# Xibeca44.net
KiCad netlist of a schematic drawn in EAGLE
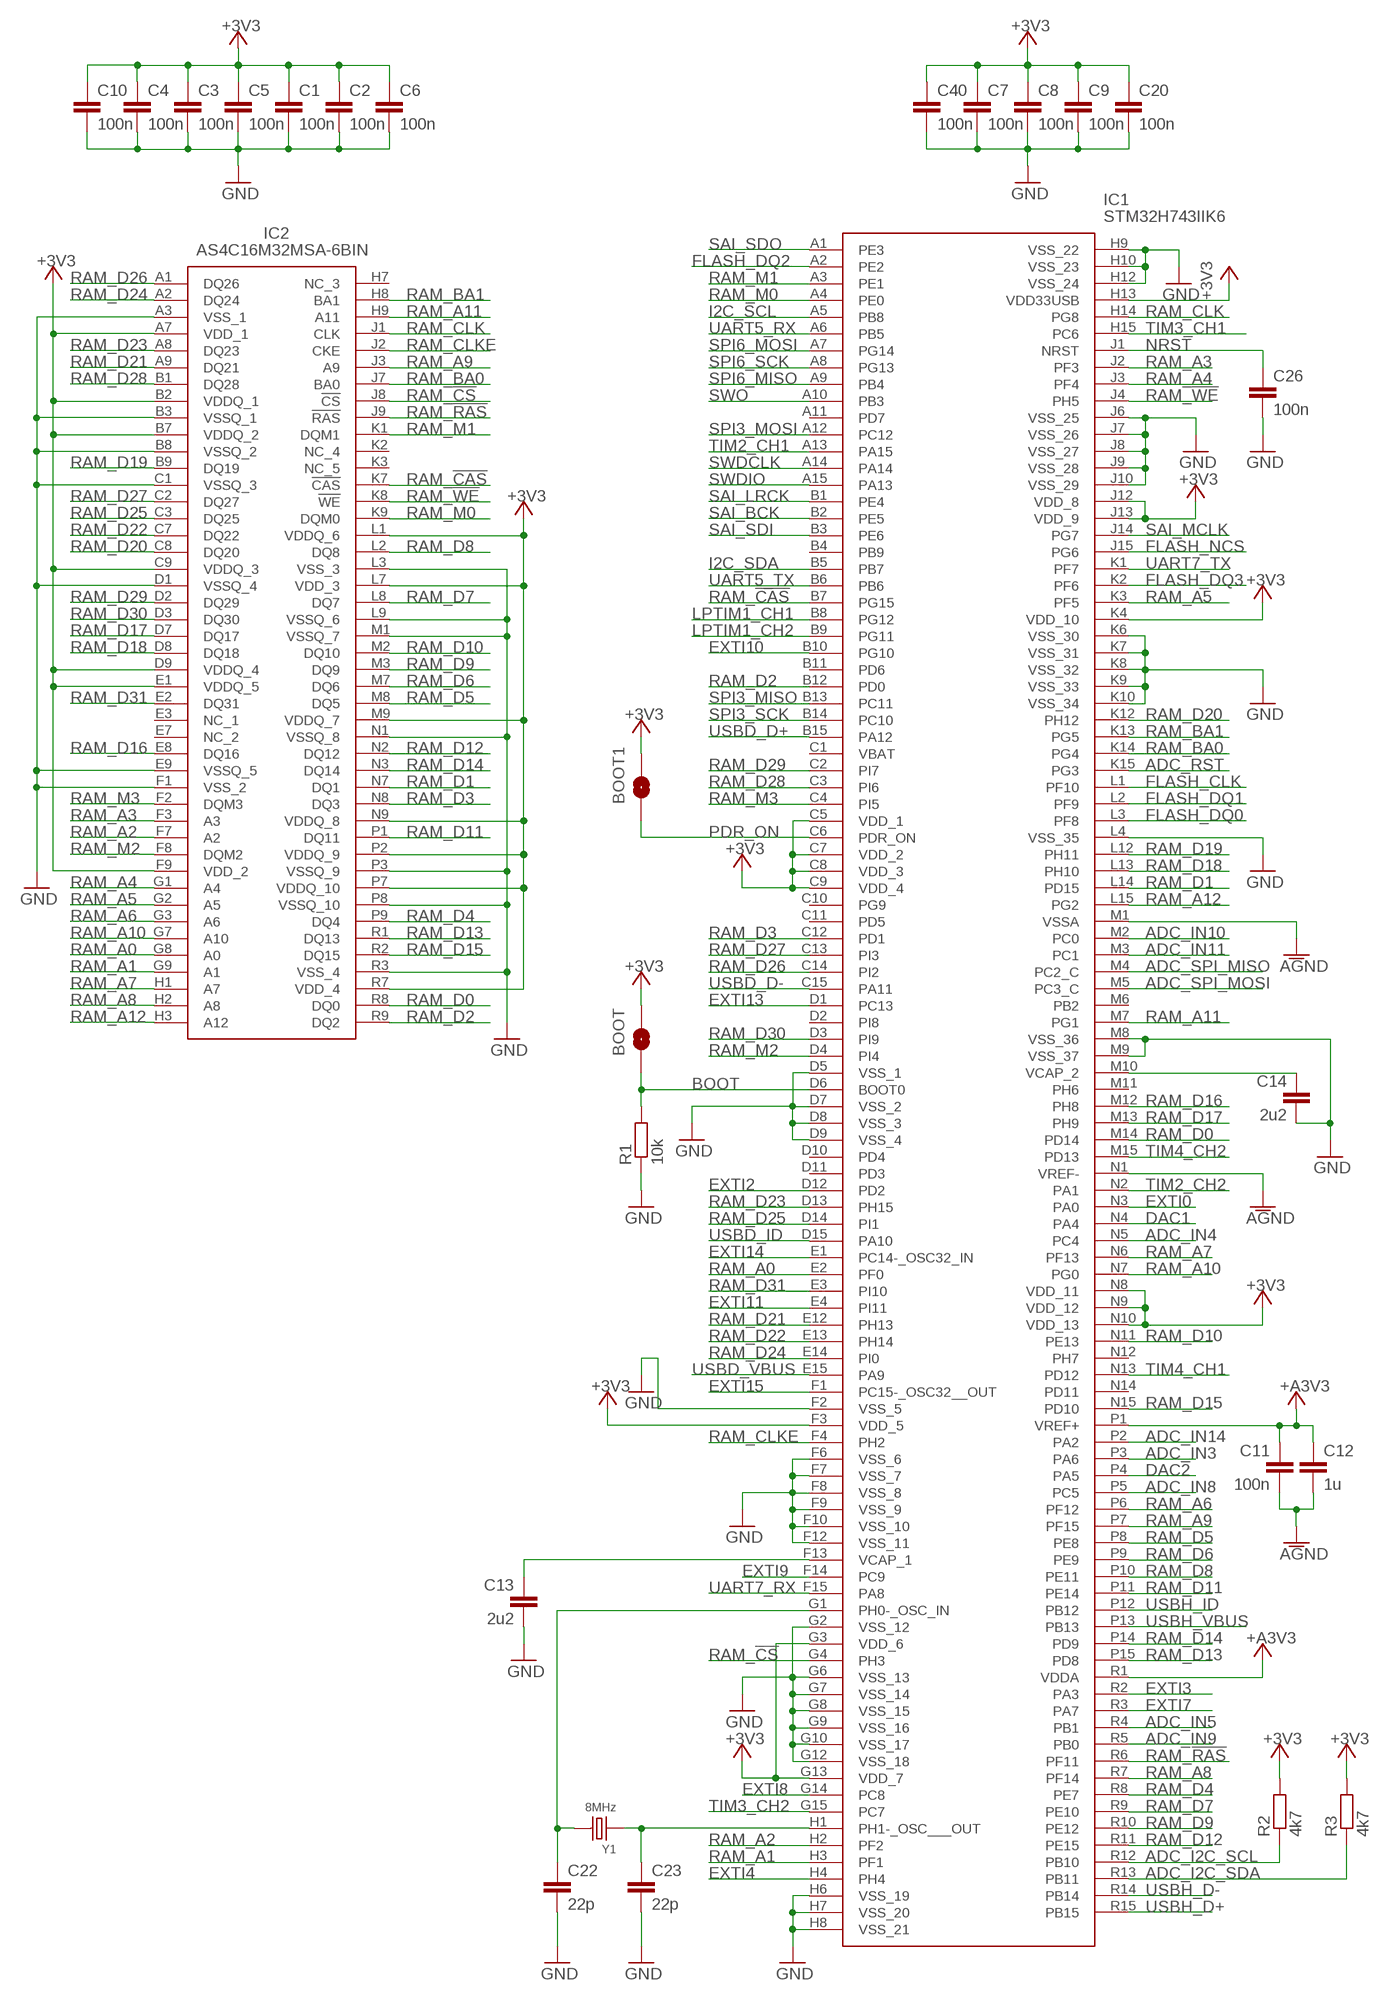
[diagram p0: schematic, sheet 1, part 1 of 2]
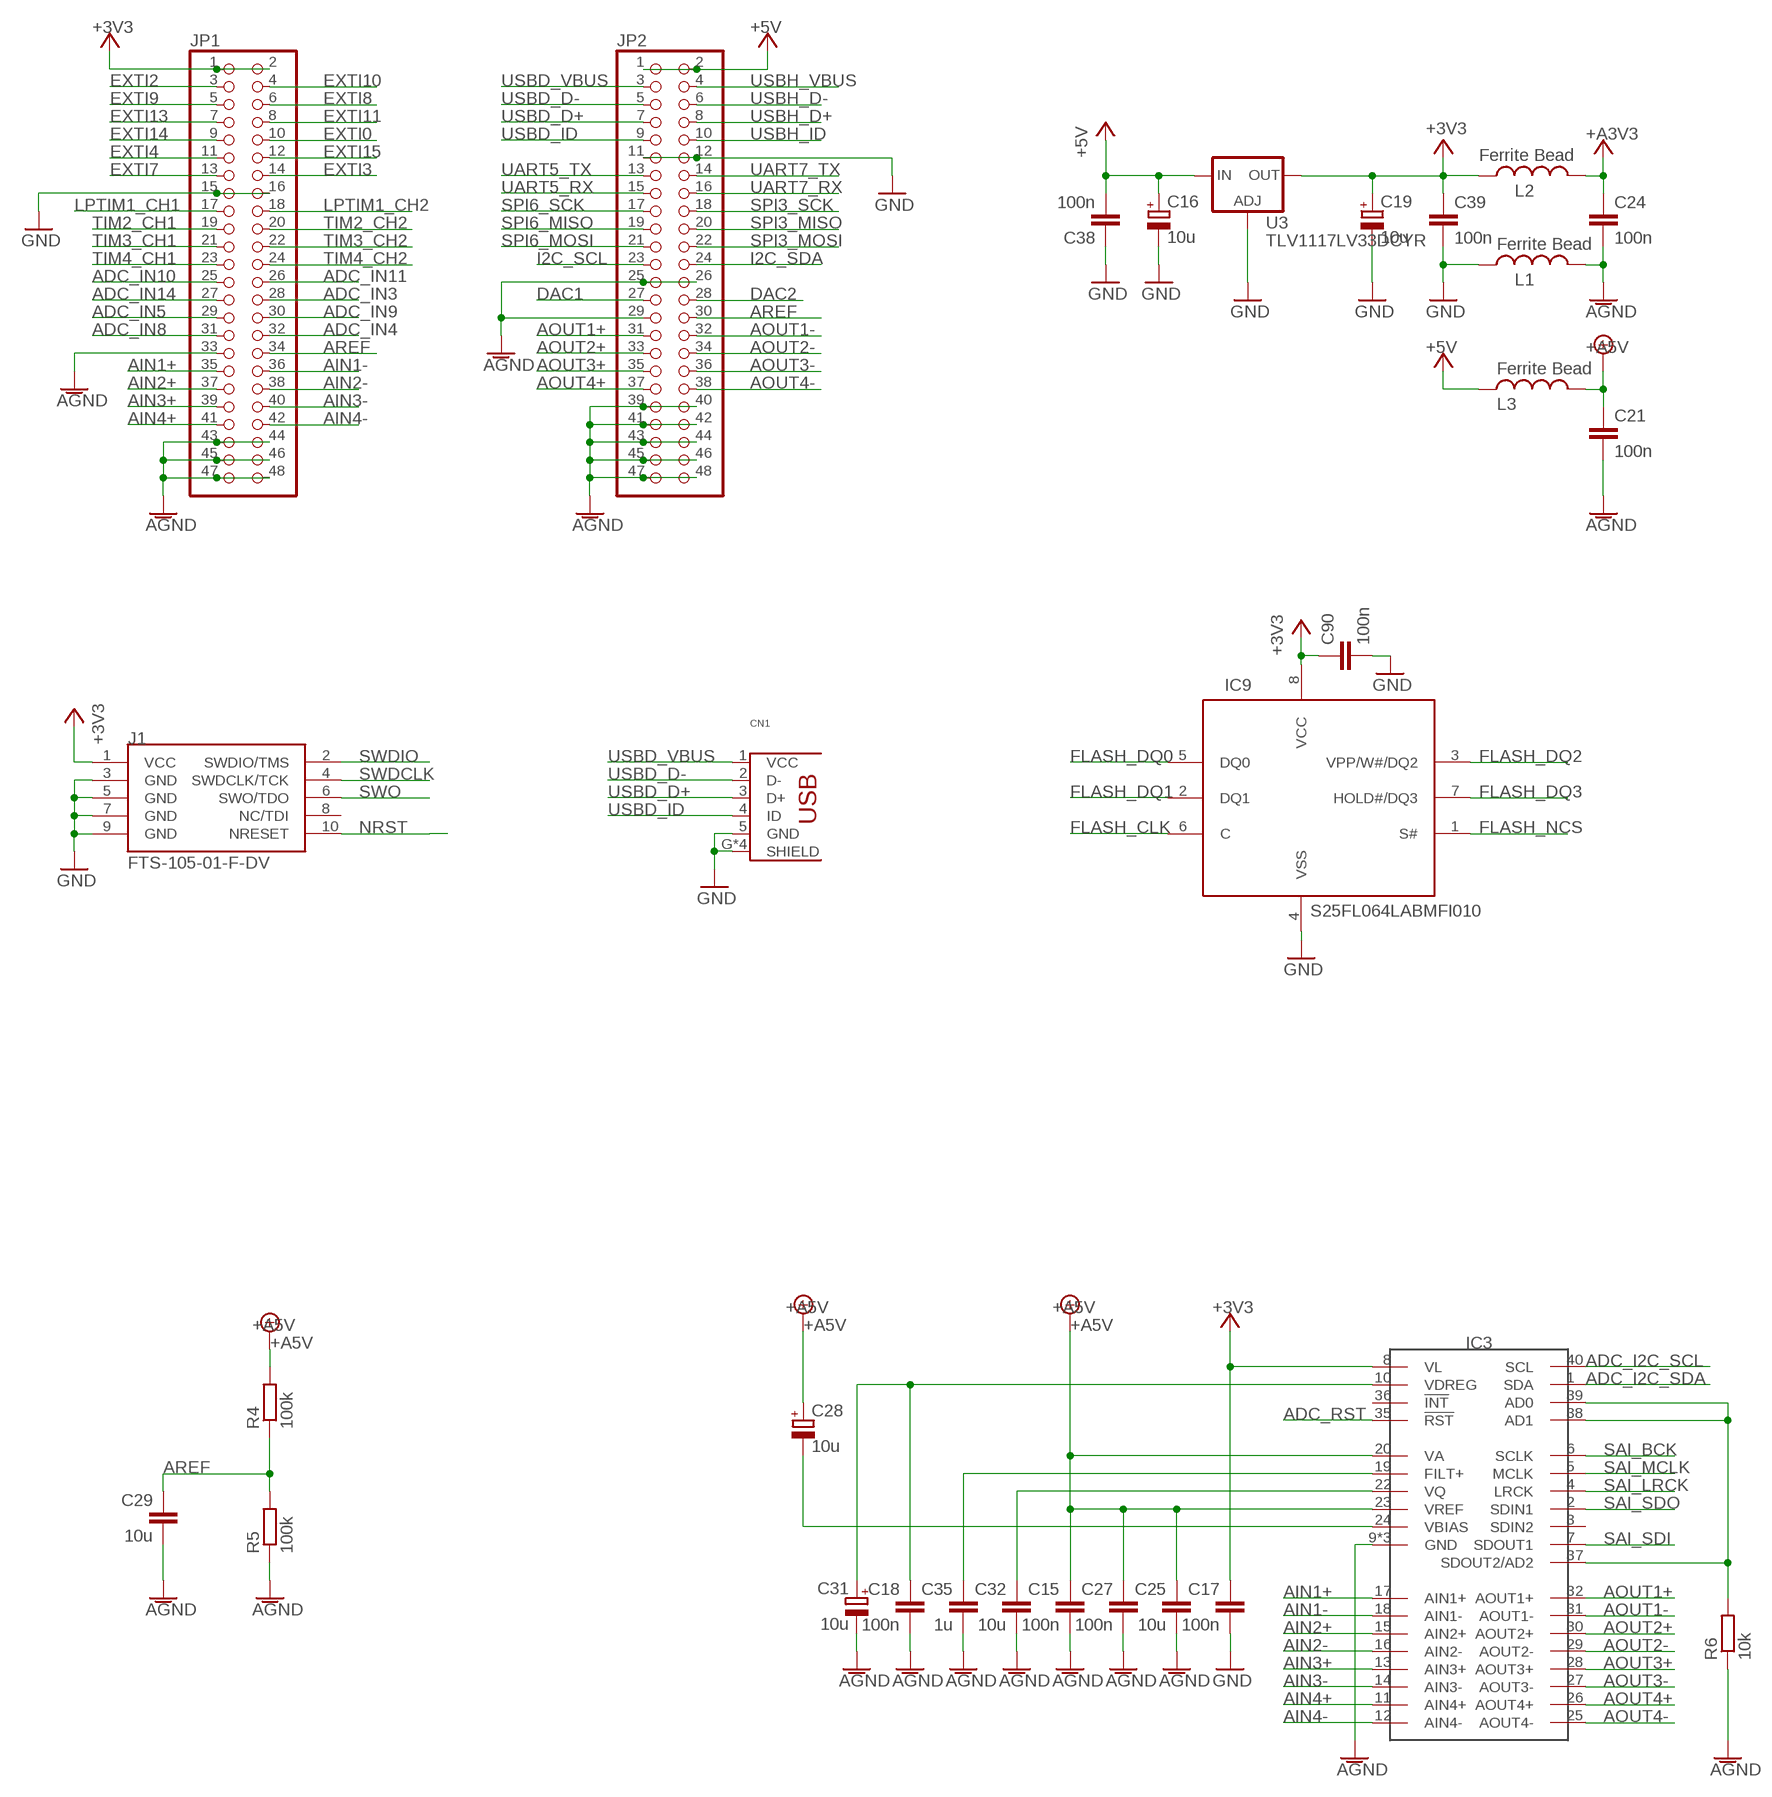
[diagram p1: schematic, sheet 1, part 2 of 2]

(export (version "E")
  (design (tool "Eeschema 10.0.6"))
  (components
    (comp (ref "BOOT")
      (value "SOLDERJUMPERNO")
      (footprint "eagle-import:SJ_2S-NO")
      (libsource (lib "eagle-import") (part "SOLDERJUMPERNO"))
    )
    (comp (ref "BOOT1")
      (value "SOLDERJUMPERNO")
      (footprint "eagle-import:SJ_2S-NO")
      (libsource (lib "eagle-import") (part "SOLDERJUMPERNO"))
    )
    (comp (ref "C1")
      (value "100n")
      (footprint "eagle-import:C0402")
      (libsource (lib "eagle-import") (part "C-EUC0402"))
    )
    (comp (ref "C2")
      (value "100n")
      (footprint "eagle-import:C0402")
      (libsource (lib "eagle-import") (part "C-EUC0402"))
    )
    (comp (ref "C3")
      (value "100n")
      (footprint "eagle-import:C0402")
      (libsource (lib "eagle-import") (part "C-EUC0402"))
    )
    (comp (ref "C4")
      (value "100n")
      (footprint "eagle-import:C0402")
      (libsource (lib "eagle-import") (part "C-EUC0402"))
    )
    (comp (ref "C5")
      (value "100n")
      (footprint "eagle-import:C0402")
      (libsource (lib "eagle-import") (part "C-EUC0402"))
    )
    (comp (ref "C6")
      (value "100n")
      (footprint "eagle-import:C0402")
      (libsource (lib "eagle-import") (part "C-EUC0402"))
    )
    (comp (ref "C7")
      (value "100n")
      (footprint "eagle-import:C0402")
      (libsource (lib "eagle-import") (part "C-EUC0402"))
    )
    (comp (ref "C8")
      (value "100n")
      (footprint "eagle-import:C0402")
      (libsource (lib "eagle-import") (part "C-EUC0402"))
    )
    (comp (ref "C9")
      (value "100n")
      (footprint "eagle-import:C0402")
      (libsource (lib "eagle-import") (part "C-EUC0402"))
    )
    (comp (ref "C10")
      (value "100n")
      (footprint "eagle-import:C0402")
      (libsource (lib "eagle-import") (part "C-EUC0402"))
    )
    (comp (ref "C11")
      (value "100n")
      (footprint "eagle-import:C0402")
      (libsource (lib "eagle-import") (part "C-EUC0402"))
    )
    (comp (ref "C12")
      (value "1u")
      (footprint "eagle-import:C0603")
      (libsource (lib "eagle-import") (part "C-EUC0603"))
    )
    (comp (ref "C13")
      (value "2u2")
      (footprint "eagle-import:C0402")
      (libsource (lib "eagle-import") (part "C-EUC0402"))
    )
    (comp (ref "C14")
      (value "2u2")
      (footprint "eagle-import:C0402")
      (libsource (lib "eagle-import") (part "C-EUC0402"))
    )
    (comp (ref "C15")
      (value "100n")
      (footprint "eagle-import:C0402")
      (libsource (lib "eagle-import") (part "C-EUC0402"))
    )
    (comp (ref "C16")
      (value "10u")
      (footprint "eagle-import:UD-4X5,8_NICHICON")
      (libsource (lib "eagle-import") (part "CPOL-EUUD-4X5,8"))
    )
    (comp (ref "C17")
      (value "100n")
      (footprint "eagle-import:C0402")
      (libsource (lib "eagle-import") (part "C-EUC0402"))
    )
    (comp (ref "C18")
      (value "100n")
      (footprint "eagle-import:C0402")
      (libsource (lib "eagle-import") (part "C-EUC0402"))
    )
    (comp (ref "C19")
      (value "10u")
      (footprint "eagle-import:UD-4X5,8_NICHICON")
      (libsource (lib "eagle-import") (part "CPOL-EUUD-4X5,8"))
    )
    (comp (ref "C20")
      (value "100n")
      (footprint "eagle-import:C0402")
      (libsource (lib "eagle-import") (part "C-EUC0402"))
    )
    (comp (ref "C21")
      (value "100n")
      (footprint "eagle-import:C0402")
      (libsource (lib "eagle-import") (part "C-EUC0402"))
    )
    (comp (ref "C22")
      (value "22p")
      (footprint "eagle-import:C0402")
      (libsource (lib "eagle-import") (part "C-EUC0402"))
    )
    (comp (ref "C23")
      (value "22p")
      (footprint "eagle-import:C0402")
      (libsource (lib "eagle-import") (part "C-EUC0402"))
    )
    (comp (ref "C24")
      (value "100n")
      (footprint "eagle-import:C0402")
      (libsource (lib "eagle-import") (part "C-EUC0402"))
    )
    (comp (ref "C25")
      (value "10u")
      (footprint "eagle-import:C0603")
      (libsource (lib "eagle-import") (part "C-EUC0603"))
    )
    (comp (ref "C26")
      (value "100n")
      (footprint "eagle-import:C0402")
      (libsource (lib "eagle-import") (part "C-EUC0402"))
    )
    (comp (ref "C27")
      (value "100n")
      (footprint "eagle-import:C0402")
      (libsource (lib "eagle-import") (part "C-EUC0402"))
    )
    (comp (ref "C28")
      (value "10u")
      (footprint "eagle-import:UD-4X5,8_NICHICON")
      (libsource (lib "eagle-import") (part "CPOL-EUUD-4X5,8"))
    )
    (comp (ref "C29")
      (value "10u")
      (footprint "eagle-import:C0603")
      (libsource (lib "eagle-import") (part "C-EUC0603"))
    )
    (comp (ref "C31")
      (value "10u")
      (footprint "eagle-import:UD-4X5,8_NICHICON")
      (libsource (lib "eagle-import") (part "CPOL-EUUD-4X5,8"))
    )
    (comp (ref "C32")
      (value "10u")
      (footprint "eagle-import:C0603")
      (libsource (lib "eagle-import") (part "C-EUC0603"))
    )
    (comp (ref "C35")
      (value "1u")
      (footprint "eagle-import:C0603")
      (libsource (lib "eagle-import") (part "C-EUC0603"))
    )
    (comp (ref "C38")
      (value "100n")
      (footprint "eagle-import:C0402")
      (libsource (lib "eagle-import") (part "C-EUC0402"))
    )
    (comp (ref "C39")
      (value "100n")
      (footprint "eagle-import:C0402")
      (libsource (lib "eagle-import") (part "C-EUC0402"))
    )
    (comp (ref "C40")
      (value "100n")
      (footprint "eagle-import:C0402")
      (libsource (lib "eagle-import") (part "C-EUC0402"))
    )
    (comp (ref "C90")
      (value "100n")
      (footprint "eagle-import:C0402")
      (libsource (lib "eagle-import") (part "C-EUC0402"))
    )
    (comp (ref "CN1")
      (value "USB_HRS_ZX62-B-5PA(11)MICRO.B")
      (footprint "eagle-import:HRS_ZX62RD-AB-5P8")
      (libsource (lib "eagle-import") (part "USB_HRS_ZX62-B-5PA(11)MICRO.B"))
    )
    (comp (ref "IC1")
      (value "STM32H743IIK6")
      (footprint "eagle-import:BGA201C65P15X15_1000X1000X60")
      (fields (field (name "MOUSER_PART_NUMBER") "511-STM32H743IIK6"))
      (libsource (lib "eagle-import") (part "STM32H743IIK6"))
    )
    (comp (ref "IC2")
      (value "AS4C16M32MSA-6BIN")
      (footprint "eagle-import:BGA90C80P9X15_800X1300X100")
      (fields (field (name "MOUSER_PART_NUMBER") "913-AS4C16M32MSA6BIN"))
      (libsource (lib "eagle-import") (part "AS4C16M32MSA-6BIN"))
    )
    (comp (ref "IC3")
      (value "CS4244")
      (footprint "eagle-import:QFN50P600X600X100-41N")
      (libsource (lib "eagle-import") (part "CS4244"))
    )
    (comp (ref "IC9")
      (value "S25FL064LABMFI010")
      (footprint "eagle-import:SO8W")
      (libsource (lib "eagle-import") (part "N25Q128A13"))
    )
    (comp (ref "J1")
      (value "FTS-105-01-F-DV")
      (footprint "eagle-import:2X5_1.27MM_SMD")
      (libsource (lib "eagle-import") (part "ARM_10SMD"))
    )
    (comp (ref "JP1")
      (value "PINHD-2X24")
      (footprint "eagle-import:2X24")
      (libsource (lib "eagle-import") (part "PINHD-2X24"))
    )
    (comp (ref "JP2")
      (value "PINHD-2X24")
      (footprint "eagle-import:2X24")
      (libsource (lib "eagle-import") (part "PINHD-2X24"))
    )
    (comp (ref "L1")
      (value "Ferrite Bead")
      (footprint "eagle-import:0603")
      (libsource (lib "eagle-import") (part "INDUCTOR"))
    )
    (comp (ref "L2")
      (value "Ferrite Bead")
      (footprint "eagle-import:0603")
      (libsource (lib "eagle-import") (part "INDUCTOR"))
    )
    (comp (ref "L3")
      (value "Ferrite Bead")
      (footprint "eagle-import:0603")
      (libsource (lib "eagle-import") (part "INDUCTOR"))
    )
    (comp (ref "R1")
      (value "10k")
      (footprint "eagle-import:R0402")
      (libsource (lib "eagle-import") (part "R-EU_R0402"))
    )
    (comp (ref "R2")
      (value "4k7")
      (footprint "eagle-import:R0402")
      (libsource (lib "eagle-import") (part "R-EU_R0402"))
    )
    (comp (ref "R3")
      (value "4k7")
      (footprint "eagle-import:R0402")
      (libsource (lib "eagle-import") (part "R-EU_R0402"))
    )
    (comp (ref "R4")
      (value "100k")
      (footprint "eagle-import:R0402")
      (libsource (lib "eagle-import") (part "R-EU_R0402"))
    )
    (comp (ref "R5")
      (value "100k")
      (footprint "eagle-import:R0402")
      (libsource (lib "eagle-import") (part "R-EU_R0402"))
    )
    (comp (ref "R6")
      (value "10k")
      (footprint "eagle-import:R0402")
      (libsource (lib "eagle-import") (part "R-EU_R0402"))
    )
    (comp (ref "U3")
      (value "TLV1117LV33DCYR")
      (footprint "eagle-import:SOT223")
      (libsource (lib "eagle-import") (part "LD117A?S33TR"))
    )
    (comp (ref "Y1")
      (value "8MHz")
      (footprint "eagle-import:X2-SMD-5.0X3.2X1.3MM")
      (fields (field (name "MPN") "5032/2P"))
      (libsource (lib "eagle-import") (part "SMD-CRYSTAL-8MHZ-20PF-20PPM(2P-5.0X3.2MM)"))
    )
  )
  (nets
    (net (code "1") (name "+3V3") (class "Default")
      (node (ref "BOOT") (pin "1") (pinfunction "1_1") (pintype "passive"))
      (node (ref "BOOT1") (pin "1") (pinfunction "1_1") (pintype "passive"))
      (node (ref "C1") (pin "1") (pinfunction "1_1") (pintype "passive"))
      (node (ref "C10") (pin "1") (pinfunction "1_1") (pintype "passive"))
      (node (ref "C17") (pin "1") (pinfunction "1_1") (pintype "passive"))
      (node (ref "C19") (pin "+") (pinfunction "+_+") (pintype "passive"))
      (node (ref "C2") (pin "1") (pinfunction "1_1") (pintype "passive"))
      (node (ref "C20") (pin "1") (pinfunction "1_1") (pintype "passive"))
      (node (ref "C3") (pin "1") (pinfunction "1_1") (pintype "passive"))
      (node (ref "C39") (pin "1") (pinfunction "1_1") (pintype "passive"))
      (node (ref "C4") (pin "1") (pinfunction "1_1") (pintype "passive"))
      (node (ref "C40") (pin "1") (pinfunction "1_1") (pintype "passive"))
      (node (ref "C5") (pin "1") (pinfunction "1_1") (pintype "passive"))
      (node (ref "C6") (pin "1") (pinfunction "1_1") (pintype "passive"))
      (node (ref "C7") (pin "1") (pinfunction "1_1") (pintype "passive"))
      (node (ref "C8") (pin "1") (pinfunction "1_1") (pintype "passive"))
      (node (ref "C9") (pin "1") (pinfunction "1_1") (pintype "passive"))
      (node (ref "C90") (pin "1") (pinfunction "1_1") (pintype "passive"))
      (node (ref "IC1") (pin "C5") (pinfunction "VDD_1_C5") (pintype "bidirectional"))
      (node (ref "IC1") (pin "C7") (pinfunction "VDD_2_C7") (pintype "bidirectional"))
      (node (ref "IC1") (pin "C8") (pinfunction "VDD_3_C8") (pintype "bidirectional"))
      (node (ref "IC1") (pin "C9") (pinfunction "VDD_4_C9") (pintype "bidirectional"))
      (node (ref "IC1") (pin "F3") (pinfunction "VDD_5_F3") (pintype "bidirectional"))
      (node (ref "IC1") (pin "G13") (pinfunction "VDD_7_G13") (pintype "bidirectional"))
      (node (ref "IC1") (pin "G3") (pinfunction "VDD_6_G3") (pintype "bidirectional"))
      (node (ref "IC1") (pin "H13") (pinfunction "VDD33USB_H13") (pintype "bidirectional"))
      (node (ref "IC1") (pin "J12") (pinfunction "VDD_8_J12") (pintype "bidirectional"))
      (node (ref "IC1") (pin "J13") (pinfunction "VDD_9_J13") (pintype "bidirectional"))
      (node (ref "IC1") (pin "K4") (pinfunction "VDD_10_K4") (pintype "bidirectional"))
      (node (ref "IC1") (pin "N10") (pinfunction "VDD_13_N10") (pintype "bidirectional"))
      (node (ref "IC1") (pin "N8") (pinfunction "VDD_11_N8") (pintype "bidirectional"))
      (node (ref "IC1") (pin "N9") (pinfunction "VDD_12_N9") (pintype "bidirectional"))
      (node (ref "IC2") (pin "A7") (pinfunction "VDD_1_A7") (pintype "bidirectional"))
      (node (ref "IC2") (pin "B2") (pinfunction "VDDQ_1_B2") (pintype "bidirectional"))
      (node (ref "IC2") (pin "B7") (pinfunction "VDDQ_2_B7") (pintype "bidirectional"))
      (node (ref "IC2") (pin "C9") (pinfunction "VDDQ_3_C9") (pintype "bidirectional"))
      (node (ref "IC2") (pin "D9") (pinfunction "VDDQ_4_D9") (pintype "bidirectional"))
      (node (ref "IC2") (pin "E1") (pinfunction "VDDQ_5_E1") (pintype "bidirectional"))
      (node (ref "IC2") (pin "F9") (pinfunction "VDD_2_F9") (pintype "bidirectional"))
      (node (ref "IC2") (pin "L1") (pinfunction "VDDQ_6_L1") (pintype "bidirectional"))
      (node (ref "IC2") (pin "L7") (pinfunction "VDD_3_L7") (pintype "bidirectional"))
      (node (ref "IC2") (pin "M9") (pinfunction "VDDQ_7_M9") (pintype "bidirectional"))
      (node (ref "IC2") (pin "N9") (pinfunction "VDDQ_8_N9") (pintype "bidirectional"))
      (node (ref "IC2") (pin "P2") (pinfunction "VDDQ_9_P2") (pintype "bidirectional"))
      (node (ref "IC2") (pin "P7") (pinfunction "VDDQ_10_P7") (pintype "bidirectional"))
      (node (ref "IC2") (pin "R7") (pinfunction "VDD_4_R7") (pintype "bidirectional"))
      (node (ref "IC3") (pin "8") (pinfunction "VL_8") (pintype "bidirectional"))
      (node (ref "IC9") (pin "8") (pinfunction "VCC_8") (pintype "bidirectional"))
      (node (ref "J1") (pin "1") (pinfunction "VCC_1") (pintype "bidirectional"))
      (node (ref "JP1") (pin "1") (pinfunction "1_1") (pintype "passive"))
      (node (ref "JP1") (pin "2") (pinfunction "2_2") (pintype "passive"))
      (node (ref "L2") (pin "2") (pinfunction "2_2") (pintype "passive"))
      (node (ref "R2") (pin "2") (pinfunction "2_2") (pintype "passive"))
      (node (ref "R3") (pin "2") (pinfunction "2_2") (pintype "passive"))
      (node (ref "U3") (pin "4") (pinfunction "OUT_4") (pintype "passive"))
    )
    (net (code "2") (name "+5V") (class "Default")
      (node (ref "C16") (pin "+") (pinfunction "+_+") (pintype "passive"))
      (node (ref "C38") (pin "2") (pinfunction "2_2") (pintype "passive"))
      (node (ref "JP2") (pin "1") (pinfunction "1_1") (pintype "passive"))
      (node (ref "JP2") (pin "2") (pinfunction "2_2") (pintype "passive"))
      (node (ref "L3") (pin "2") (pinfunction "2_2") (pintype "passive"))
      (node (ref "U3") (pin "3") (pinfunction "IN_3") (pintype "input"))
    )
    (net (code "3") (name "+A3V3") (class "Default")
      (node (ref "C11") (pin "1") (pinfunction "1_1") (pintype "passive"))
      (node (ref "C12") (pin "1") (pinfunction "1_1") (pintype "passive"))
      (node (ref "C24") (pin "1") (pinfunction "1_1") (pintype "passive"))
      (node (ref "IC1") (pin "P1") (pinfunction "VREF+_P1") (pintype "bidirectional"))
      (node (ref "IC1") (pin "R1") (pinfunction "VDDA_R1") (pintype "bidirectional"))
      (node (ref "L2") (pin "1") (pinfunction "1_1") (pintype "passive"))
    )
    (net (code "4") (name "+A5V") (class "Default")
      (node (ref "C15") (pin "1") (pinfunction "1_1") (pintype "passive"))
      (node (ref "C21") (pin "1") (pinfunction "1_1") (pintype "passive"))
      (node (ref "C25") (pin "1") (pinfunction "1_1") (pintype "passive"))
      (node (ref "C27") (pin "1") (pinfunction "1_1") (pintype "passive"))
      (node (ref "C28") (pin "+") (pinfunction "+_+") (pintype "passive"))
      (node (ref "IC3") (pin "20") (pinfunction "VA_20") (pintype "bidirectional"))
      (node (ref "IC3") (pin "23") (pinfunction "VREF_23") (pintype "bidirectional"))
      (node (ref "L3") (pin "1") (pinfunction "1_1") (pintype "passive"))
      (node (ref "R4") (pin "2") (pinfunction "2_2") (pintype "passive"))
    )
    (net (code "5") (name "/ADC_I2C_SCL") (class "Default")
      (node (ref "IC1") (pin "R12") (pinfunction "PB10_R12") (pintype "bidirectional"))
      (node (ref "IC3") (pin "40") (pinfunction "SCL_40") (pintype "bidirectional"))
      (node (ref "R2") (pin "1") (pinfunction "1_1") (pintype "passive"))
    )
    (net (code "6") (name "/ADC_I2C_SDA") (class "Default")
      (node (ref "IC1") (pin "R13") (pinfunction "PB11_R13") (pintype "bidirectional"))
      (node (ref "IC3") (pin "1") (pinfunction "SDA_1") (pintype "bidirectional"))
      (node (ref "R3") (pin "1") (pinfunction "1_1") (pintype "passive"))
    )
    (net (code "7") (name "/ADC_IN3") (class "Default")
      (node (ref "IC1") (pin "P3") (pinfunction "PA6_P3") (pintype "bidirectional"))
      (node (ref "JP1") (pin "28") (pinfunction "28_28") (pintype "passive"))
    )
    (net (code "8") (name "/ADC_IN4") (class "Default")
      (node (ref "IC1") (pin "N5") (pinfunction "PC4_N5") (pintype "bidirectional"))
      (node (ref "JP1") (pin "32") (pinfunction "32_32") (pintype "passive"))
    )
    (net (code "9") (name "/ADC_IN5") (class "Default")
      (node (ref "IC1") (pin "R4") (pinfunction "PB1_R4") (pintype "bidirectional"))
      (node (ref "JP1") (pin "29") (pinfunction "29_29") (pintype "passive"))
    )
    (net (code "10") (name "/ADC_IN8") (class "Default")
      (node (ref "IC1") (pin "P5") (pinfunction "PC5_P5") (pintype "bidirectional"))
      (node (ref "JP1") (pin "31") (pinfunction "31_31") (pintype "passive"))
    )
    (net (code "11") (name "/ADC_IN9") (class "Default")
      (node (ref "IC1") (pin "R5") (pinfunction "PB0_R5") (pintype "bidirectional"))
      (node (ref "JP1") (pin "30") (pinfunction "30_30") (pintype "passive"))
    )
    (net (code "12") (name "/ADC_IN10") (class "Default")
      (node (ref "IC1") (pin "M2") (pinfunction "PC0_M2") (pintype "bidirectional"))
      (node (ref "JP1") (pin "25") (pinfunction "25_25") (pintype "passive"))
    )
    (net (code "13") (name "/ADC_IN11") (class "Default")
      (node (ref "IC1") (pin "M3") (pinfunction "PC1_M3") (pintype "bidirectional"))
      (node (ref "JP1") (pin "26") (pinfunction "26_26") (pintype "passive"))
    )
    (net (code "14") (name "/ADC_IN14") (class "Default")
      (node (ref "IC1") (pin "P2") (pinfunction "PA2_P2") (pintype "bidirectional"))
      (node (ref "JP1") (pin "27") (pinfunction "27_27") (pintype "passive"))
    )
    (net (code "15") (name "/ADC_RST") (class "Default")
      (node (ref "IC1") (pin "K15") (pinfunction "PG3_K15") (pintype "bidirectional"))
      (node (ref "IC3") (pin "35") (pinfunction "~{RST}_35") (pintype "bidirectional"))
    )
    (net (code "16") (name "/ADC_SPI_MISO") (class "Default")
      (node (ref "IC1") (pin "M4") (pinfunction "PC2_C_M4") (pintype "bidirectional"))
    )
    (net (code "17") (name "/ADC_SPI_MOSI") (class "Default")
      (node (ref "IC1") (pin "M5") (pinfunction "PC3_C_M5") (pintype "bidirectional"))
    )
    (net (code "18") (name "/AIN1+") (class "Default")
      (node (ref "IC3") (pin "17") (pinfunction "AIN1+_17") (pintype "bidirectional"))
      (node (ref "JP1") (pin "35") (pinfunction "35_35") (pintype "passive"))
    )
    (net (code "19") (name "/AIN1-") (class "Default")
      (node (ref "IC3") (pin "18") (pinfunction "AIN1-_18") (pintype "bidirectional"))
      (node (ref "JP1") (pin "36") (pinfunction "36_36") (pintype "passive"))
    )
    (net (code "20") (name "/AIN2+") (class "Default")
      (node (ref "IC3") (pin "15") (pinfunction "AIN2+_15") (pintype "bidirectional"))
      (node (ref "JP1") (pin "37") (pinfunction "37_37") (pintype "passive"))
    )
    (net (code "21") (name "/AIN2-") (class "Default")
      (node (ref "IC3") (pin "16") (pinfunction "AIN2-_16") (pintype "bidirectional"))
      (node (ref "JP1") (pin "38") (pinfunction "38_38") (pintype "passive"))
    )
    (net (code "22") (name "/AIN3+") (class "Default")
      (node (ref "IC3") (pin "13") (pinfunction "AIN3+_13") (pintype "bidirectional"))
      (node (ref "JP1") (pin "39") (pinfunction "39_39") (pintype "passive"))
    )
    (net (code "23") (name "/AIN3-") (class "Default")
      (node (ref "IC3") (pin "14") (pinfunction "AIN3-_14") (pintype "bidirectional"))
      (node (ref "JP1") (pin "40") (pinfunction "40_40") (pintype "passive"))
    )
    (net (code "24") (name "/AIN4+") (class "Default")
      (node (ref "IC3") (pin "11") (pinfunction "AIN4+_11") (pintype "bidirectional"))
      (node (ref "JP1") (pin "41") (pinfunction "41_41") (pintype "passive"))
    )
    (net (code "25") (name "/AIN4-") (class "Default")
      (node (ref "IC3") (pin "12") (pinfunction "AIN4-_12") (pintype "bidirectional"))
      (node (ref "JP1") (pin "42") (pinfunction "42_42") (pintype "passive"))
    )
    (net (code "26") (name "/AOUT1+") (class "Default")
      (node (ref "IC3") (pin "32") (pinfunction "AOUT1+_32") (pintype "bidirectional"))
      (node (ref "JP2") (pin "31") (pinfunction "31_31") (pintype "passive"))
    )
    (net (code "27") (name "/AOUT1-") (class "Default")
      (node (ref "IC3") (pin "31") (pinfunction "AOUT1-_31") (pintype "bidirectional"))
      (node (ref "JP2") (pin "32") (pinfunction "32_32") (pintype "passive"))
    )
    (net (code "28") (name "/AOUT2+") (class "Default")
      (node (ref "IC3") (pin "30") (pinfunction "AOUT2+_30") (pintype "bidirectional"))
      (node (ref "JP2") (pin "33") (pinfunction "33_33") (pintype "passive"))
    )
    (net (code "29") (name "/AOUT2-") (class "Default")
      (node (ref "IC3") (pin "29") (pinfunction "AOUT2-_29") (pintype "bidirectional"))
      (node (ref "JP2") (pin "34") (pinfunction "34_34") (pintype "passive"))
    )
    (net (code "30") (name "/AOUT3+") (class "Default")
      (node (ref "IC3") (pin "28") (pinfunction "AOUT3+_28") (pintype "bidirectional"))
      (node (ref "JP2") (pin "35") (pinfunction "35_35") (pintype "passive"))
    )
    (net (code "31") (name "/AOUT3-") (class "Default")
      (node (ref "IC3") (pin "27") (pinfunction "AOUT3-_27") (pintype "bidirectional"))
      (node (ref "JP2") (pin "36") (pinfunction "36_36") (pintype "passive"))
    )
    (net (code "32") (name "/AOUT4+") (class "Default")
      (node (ref "IC3") (pin "26") (pinfunction "AOUT4+_26") (pintype "bidirectional"))
      (node (ref "JP2") (pin "37") (pinfunction "37_37") (pintype "passive"))
    )
    (net (code "33") (name "/AOUT4-") (class "Default")
      (node (ref "IC3") (pin "25") (pinfunction "AOUT4-_25") (pintype "bidirectional"))
      (node (ref "JP2") (pin "38") (pinfunction "38_38") (pintype "passive"))
    )
    (net (code "34") (name "/AREF") (class "Default")
      (node (ref "C29") (pin "1") (pinfunction "1_1") (pintype "passive"))
      (node (ref "JP1") (pin "34") (pinfunction "34_34") (pintype "passive"))
      (node (ref "JP2") (pin "30") (pinfunction "30_30") (pintype "passive"))
      (node (ref "R4") (pin "1") (pinfunction "1_1") (pintype "passive"))
      (node (ref "R5") (pin "2") (pinfunction "2_2") (pintype "passive"))
    )
    (net (code "35") (name "/BOOT") (class "Default")
      (node (ref "BOOT") (pin "2") (pinfunction "2_2") (pintype "passive"))
      (node (ref "IC1") (pin "D6") (pinfunction "BOOT0_D6") (pintype "bidirectional"))
      (node (ref "R1") (pin "2") (pinfunction "2_2") (pintype "passive"))
    )
    (net (code "36") (name "/DAC1") (class "Default")
      (node (ref "IC1") (pin "N4") (pinfunction "PA4_N4") (pintype "bidirectional"))
      (node (ref "JP2") (pin "27") (pinfunction "27_27") (pintype "passive"))
    )
    (net (code "37") (name "/DAC2") (class "Default")
      (node (ref "IC1") (pin "P4") (pinfunction "PA5_P4") (pintype "bidirectional"))
      (node (ref "JP2") (pin "28") (pinfunction "28_28") (pintype "passive"))
    )
    (net (code "38") (name "/EXTI0") (class "Default")
      (node (ref "IC1") (pin "N3") (pinfunction "PA0_N3") (pintype "bidirectional"))
      (node (ref "JP1") (pin "10") (pinfunction "10_10") (pintype "passive"))
    )
    (net (code "39") (name "/EXTI2") (class "Default")
      (node (ref "IC1") (pin "D12") (pinfunction "PD2_D12") (pintype "bidirectional"))
      (node (ref "JP1") (pin "3") (pinfunction "3_3") (pintype "passive"))
    )
    (net (code "40") (name "/EXTI3") (class "Default")
      (node (ref "IC1") (pin "R2") (pinfunction "PA3_R2") (pintype "bidirectional"))
      (node (ref "JP1") (pin "14") (pinfunction "14_14") (pintype "passive"))
    )
    (net (code "41") (name "/EXTI4") (class "Default")
      (node (ref "IC1") (pin "H4") (pinfunction "PH4_H4") (pintype "bidirectional"))
      (node (ref "JP1") (pin "11") (pinfunction "11_11") (pintype "passive"))
    )
    (net (code "42") (name "/EXTI7") (class "Default")
      (node (ref "IC1") (pin "R3") (pinfunction "PA7_R3") (pintype "bidirectional"))
      (node (ref "JP1") (pin "13") (pinfunction "13_13") (pintype "passive"))
    )
    (net (code "43") (name "/EXTI8") (class "Default")
      (node (ref "IC1") (pin "G14") (pinfunction "PC8_G14") (pintype "bidirectional"))
      (node (ref "JP1") (pin "6") (pinfunction "6_6") (pintype "passive"))
    )
    (net (code "44") (name "/EXTI9") (class "Default")
      (node (ref "IC1") (pin "F14") (pinfunction "PC9_F14") (pintype "bidirectional"))
      (node (ref "JP1") (pin "5") (pinfunction "5_5") (pintype "passive"))
    )
    (net (code "45") (name "/EXTI10") (class "Default")
      (node (ref "IC1") (pin "B10") (pinfunction "PG10_B10") (pintype "bidirectional"))
      (node (ref "JP1") (pin "4") (pinfunction "4_4") (pintype "passive"))
    )
    (net (code "46") (name "/EXTI11") (class "Default")
      (node (ref "IC1") (pin "E4") (pinfunction "PI11_E4") (pintype "bidirectional"))
      (node (ref "JP1") (pin "8") (pinfunction "8_8") (pintype "passive"))
    )
    (net (code "47") (name "/EXTI13") (class "Default")
      (node (ref "IC1") (pin "D1") (pinfunction "PC13_D1") (pintype "bidirectional"))
      (node (ref "JP1") (pin "7") (pinfunction "7_7") (pintype "passive"))
    )
    (net (code "48") (name "/EXTI14") (class "Default")
      (node (ref "IC1") (pin "E1") (pinfunction "PC14-_OSC32_IN_E1") (pintype "bidirectional"))
      (node (ref "JP1") (pin "9") (pinfunction "9_9") (pintype "passive"))
    )
    (net (code "49") (name "/EXTI15") (class "Default")
      (node (ref "IC1") (pin "F1") (pinfunction "PC15-_OSC32__OUT_F1") (pintype "bidirectional"))
      (node (ref "JP1") (pin "12") (pinfunction "12_12") (pintype "passive"))
    )
    (net (code "50") (name "/FLASH_CLK") (class "Default")
      (node (ref "IC1") (pin "L1") (pinfunction "PF10_L1") (pintype "bidirectional"))
      (node (ref "IC9") (pin "6") (pinfunction "C_6") (pintype "bidirectional"))
    )
    (net (code "51") (name "/FLASH_DQ0") (class "Default")
      (node (ref "IC1") (pin "L3") (pinfunction "PF8_L3") (pintype "bidirectional"))
      (node (ref "IC9") (pin "5") (pinfunction "DQ0_5") (pintype "bidirectional"))
    )
    (net (code "52") (name "/FLASH_DQ1") (class "Default")
      (node (ref "IC1") (pin "L2") (pinfunction "PF9_L2") (pintype "bidirectional"))
      (node (ref "IC9") (pin "2") (pinfunction "DQ1_2") (pintype "bidirectional"))
    )
    (net (code "53") (name "/FLASH_DQ2") (class "Default")
      (node (ref "IC1") (pin "A2") (pinfunction "PE2_A2") (pintype "bidirectional"))
      (node (ref "IC9") (pin "3") (pinfunction "VPP/W#/DQ2_3") (pintype "bidirectional"))
    )
    (net (code "54") (name "/FLASH_DQ3") (class "Default")
      (node (ref "IC1") (pin "K2") (pinfunction "PF6_K2") (pintype "bidirectional"))
      (node (ref "IC9") (pin "7") (pinfunction "HOLD#/DQ3_7") (pintype "bidirectional"))
    )
    (net (code "55") (name "/FLASH_NCS") (class "Default")
      (node (ref "IC1") (pin "J15") (pinfunction "PG6_J15") (pintype "bidirectional"))
      (node (ref "IC9") (pin "1") (pinfunction "S#_1") (pintype "bidirectional"))
    )
    (net (code "56") (name "/I2C_SCL") (class "Default")
      (node (ref "IC1") (pin "A5") (pinfunction "PB8_A5") (pintype "bidirectional"))
      (node (ref "JP2") (pin "23") (pinfunction "23_23") (pintype "passive"))
    )
    (net (code "57") (name "/I2C_SDA") (class "Default")
      (node (ref "IC1") (pin "B5") (pinfunction "PB7_B5") (pintype "bidirectional"))
      (node (ref "JP2") (pin "24") (pinfunction "24_24") (pintype "passive"))
    )
    (net (code "58") (name "/LPTIM1_CH1") (class "Default")
      (node (ref "IC1") (pin "B8") (pinfunction "PG12_B8") (pintype "bidirectional"))
      (node (ref "JP1") (pin "17") (pinfunction "17_17") (pintype "passive"))
    )
    (net (code "59") (name "/LPTIM1_CH2") (class "Default")
      (node (ref "IC1") (pin "B9") (pinfunction "PG11_B9") (pintype "bidirectional"))
      (node (ref "JP1") (pin "18") (pinfunction "18_18") (pintype "passive"))
    )
    (net (code "60") (name "/NRST") (class "Default")
      (node (ref "C26") (pin "1") (pinfunction "1_1") (pintype "passive"))
      (node (ref "IC1") (pin "J1") (pinfunction "NRST_J1") (pintype "bidirectional"))
      (node (ref "J1") (pin "10") (pinfunction "NRESET_10") (pintype "bidirectional"))
    )
    (net (code "61") (name "/PDR_ON") (class "Default")
      (node (ref "BOOT1") (pin "2") (pinfunction "2_2") (pintype "passive"))
      (node (ref "IC1") (pin "C6") (pinfunction "PDR_ON_C6") (pintype "bidirectional"))
    )
    (net (code "62") (name "/RAM_A0") (class "Default")
      (node (ref "IC1") (pin "E2") (pinfunction "PF0_E2") (pintype "bidirectional"))
      (node (ref "IC2") (pin "G8") (pinfunction "A0_G8") (pintype "bidirectional"))
    )
    (net (code "63") (name "/RAM_A1") (class "Default")
      (node (ref "IC1") (pin "H3") (pinfunction "PF1_H3") (pintype "bidirectional"))
      (node (ref "IC2") (pin "G9") (pinfunction "A1_G9") (pintype "bidirectional"))
    )
    (net (code "64") (name "/RAM_A2") (class "Default")
      (node (ref "IC1") (pin "H2") (pinfunction "PF2_H2") (pintype "bidirectional"))
      (node (ref "IC2") (pin "F7") (pinfunction "A2_F7") (pintype "bidirectional"))
    )
    (net (code "65") (name "/RAM_A3") (class "Default")
      (node (ref "IC1") (pin "J2") (pinfunction "PF3_J2") (pintype "bidirectional"))
      (node (ref "IC2") (pin "F3") (pinfunction "A3_F3") (pintype "bidirectional"))
    )
    (net (code "66") (name "/RAM_A4") (class "Default")
      (node (ref "IC1") (pin "J3") (pinfunction "PF4_J3") (pintype "bidirectional"))
      (node (ref "IC2") (pin "G1") (pinfunction "A4_G1") (pintype "bidirectional"))
    )
    (net (code "67") (name "/RAM_A5") (class "Default")
      (node (ref "IC1") (pin "K3") (pinfunction "PF5_K3") (pintype "bidirectional"))
      (node (ref "IC2") (pin "G2") (pinfunction "A5_G2") (pintype "bidirectional"))
    )
    (net (code "68") (name "/RAM_A6") (class "Default")
      (node (ref "IC1") (pin "P6") (pinfunction "PF12_P6") (pintype "bidirectional"))
      (node (ref "IC2") (pin "G3") (pinfunction "A6_G3") (pintype "bidirectional"))
    )
    (net (code "69") (name "/RAM_A7") (class "Default")
      (node (ref "IC1") (pin "N6") (pinfunction "PF13_N6") (pintype "bidirectional"))
      (node (ref "IC2") (pin "H1") (pinfunction "A7_H1") (pintype "bidirectional"))
    )
    (net (code "70") (name "/RAM_A8") (class "Default")
      (node (ref "IC1") (pin "R7") (pinfunction "PF14_R7") (pintype "bidirectional"))
      (node (ref "IC2") (pin "H2") (pinfunction "A8_H2") (pintype "bidirectional"))
    )
    (net (code "71") (name "/RAM_A9") (class "Default")
      (node (ref "IC1") (pin "P7") (pinfunction "PF15_P7") (pintype "bidirectional"))
      (node (ref "IC2") (pin "J3") (pinfunction "A9_J3") (pintype "bidirectional"))
    )
    (net (code "72") (name "/RAM_A10") (class "Default")
      (node (ref "IC1") (pin "N7") (pinfunction "PG0_N7") (pintype "bidirectional"))
      (node (ref "IC2") (pin "G7") (pinfunction "A10_G7") (pintype "bidirectional"))
    )
    (net (code "73") (name "/RAM_A11") (class "Default")
      (node (ref "IC1") (pin "M7") (pinfunction "PG1_M7") (pintype "bidirectional"))
      (node (ref "IC2") (pin "H9") (pinfunction "A11_H9") (pintype "bidirectional"))
    )
    (net (code "74") (name "/RAM_A12") (class "Default")
      (node (ref "IC1") (pin "L15") (pinfunction "PG2_L15") (pintype "bidirectional"))
      (node (ref "IC2") (pin "H3") (pinfunction "A12_H3") (pintype "bidirectional"))
    )
    (net (code "75") (name "/RAM_BA0") (class "Default")
      (node (ref "IC1") (pin "K14") (pinfunction "PG4_K14") (pintype "bidirectional"))
      (node (ref "IC2") (pin "J7") (pinfunction "BA0_J7") (pintype "bidirectional"))
    )
    (net (code "76") (name "/RAM_BA1") (class "Default")
      (node (ref "IC1") (pin "K13") (pinfunction "PG5_K13") (pintype "bidirectional"))
      (node (ref "IC2") (pin "H8") (pinfunction "BA1_H8") (pintype "bidirectional"))
    )
    (net (code "77") (name "/RAM_CLK") (class "Default")
      (node (ref "IC1") (pin "H14") (pinfunction "PG8_H14") (pintype "bidirectional"))
      (node (ref "IC2") (pin "J1") (pinfunction "CLK_J1") (pintype "bidirectional"))
    )
    (net (code "78") (name "/RAM_CLKE") (class "Default")
      (node (ref "IC1") (pin "F4") (pinfunction "PH2_F4") (pintype "bidirectional"))
      (node (ref "IC2") (pin "J2") (pinfunction "CKE_J2") (pintype "bidirectional"))
    )
    (net (code "79") (name "/RAM_D0") (class "Default")
      (node (ref "IC1") (pin "M14") (pinfunction "PD14_M14") (pintype "bidirectional"))
      (node (ref "IC2") (pin "R8") (pinfunction "DQ0_R8") (pintype "bidirectional"))
    )
    (net (code "80") (name "/RAM_D1") (class "Default")
      (node (ref "IC1") (pin "L14") (pinfunction "PD15_L14") (pintype "bidirectional"))
      (node (ref "IC2") (pin "N7") (pinfunction "DQ1_N7") (pintype "bidirectional"))
    )
    (net (code "81") (name "/RAM_D2") (class "Default")
      (node (ref "IC1") (pin "B12") (pinfunction "PD0_B12") (pintype "bidirectional"))
      (node (ref "IC2") (pin "R9") (pinfunction "DQ2_R9") (pintype "bidirectional"))
    )
    (net (code "82") (name "/RAM_D3") (class "Default")
      (node (ref "IC1") (pin "C12") (pinfunction "PD1_C12") (pintype "bidirectional"))
      (node (ref "IC2") (pin "N8") (pinfunction "DQ3_N8") (pintype "bidirectional"))
    )
    (net (code "83") (name "/RAM_D4") (class "Default")
      (node (ref "IC1") (pin "R8") (pinfunction "PE7_R8") (pintype "bidirectional"))
      (node (ref "IC2") (pin "P9") (pinfunction "DQ4_P9") (pintype "bidirectional"))
    )
    (net (code "84") (name "/RAM_D5") (class "Default")
      (node (ref "IC1") (pin "P8") (pinfunction "PE8_P8") (pintype "bidirectional"))
      (node (ref "IC2") (pin "M8") (pinfunction "DQ5_M8") (pintype "bidirectional"))
    )
    (net (code "85") (name "/RAM_D6") (class "Default")
      (node (ref "IC1") (pin "P9") (pinfunction "PE9_P9") (pintype "bidirectional"))
      (node (ref "IC2") (pin "M7") (pinfunction "DQ6_M7") (pintype "bidirectional"))
    )
    (net (code "86") (name "/RAM_D7") (class "Default")
      (node (ref "IC1") (pin "R9") (pinfunction "PE10_R9") (pintype "bidirectional"))
      (node (ref "IC2") (pin "L8") (pinfunction "DQ7_L8") (pintype "bidirectional"))
    )
    (net (code "87") (name "/RAM_D8") (class "Default")
      (node (ref "IC1") (pin "P10") (pinfunction "PE11_P10") (pintype "bidirectional"))
      (node (ref "IC2") (pin "L2") (pinfunction "DQ8_L2") (pintype "bidirectional"))
    )
    (net (code "88") (name "/RAM_D9") (class "Default")
      (node (ref "IC1") (pin "R10") (pinfunction "PE12_R10") (pintype "bidirectional"))
      (node (ref "IC2") (pin "M3") (pinfunction "DQ9_M3") (pintype "bidirectional"))
    )
    (net (code "89") (name "/RAM_D10") (class "Default")
      (node (ref "IC1") (pin "N11") (pinfunction "PE13_N11") (pintype "bidirectional"))
      (node (ref "IC2") (pin "M2") (pinfunction "DQ10_M2") (pintype "bidirectional"))
    )
    (net (code "90") (name "/RAM_D11") (class "Default")
      (node (ref "IC1") (pin "P11") (pinfunction "PE14_P11") (pintype "bidirectional"))
      (node (ref "IC2") (pin "P1") (pinfunction "DQ11_P1") (pintype "bidirectional"))
    )
    (net (code "91") (name "/RAM_D12") (class "Default")
      (node (ref "IC1") (pin "R11") (pinfunction "PE15_R11") (pintype "bidirectional"))
      (node (ref "IC2") (pin "N2") (pinfunction "DQ12_N2") (pintype "bidirectional"))
    )
    (net (code "92") (name "/RAM_D13") (class "Default")
      (node (ref "IC1") (pin "P15") (pinfunction "PD8_P15") (pintype "bidirectional"))
      (node (ref "IC2") (pin "R1") (pinfunction "DQ13_R1") (pintype "bidirectional"))
    )
    (net (code "93") (name "/RAM_D14") (class "Default")
      (node (ref "IC1") (pin "P14") (pinfunction "PD9_P14") (pintype "bidirectional"))
      (node (ref "IC2") (pin "N3") (pinfunction "DQ14_N3") (pintype "bidirectional"))
    )
    (net (code "94") (name "/RAM_D15") (class "Default")
      (node (ref "IC1") (pin "N15") (pinfunction "PD10_N15") (pintype "bidirectional"))
      (node (ref "IC2") (pin "R2") (pinfunction "DQ15_R2") (pintype "bidirectional"))
    )
    (net (code "95") (name "/RAM_D16") (class "Default")
      (node (ref "IC1") (pin "M12") (pinfunction "PH8_M12") (pintype "bidirectional"))
      (node (ref "IC2") (pin "E8") (pinfunction "DQ16_E8") (pintype "bidirectional"))
    )
    (net (code "96") (name "/RAM_D17") (class "Default")
      (node (ref "IC1") (pin "M13") (pinfunction "PH9_M13") (pintype "bidirectional"))
      (node (ref "IC2") (pin "D7") (pinfunction "DQ17_D7") (pintype "bidirectional"))
    )
    (net (code "97") (name "/RAM_D18") (class "Default")
      (node (ref "IC1") (pin "L13") (pinfunction "PH10_L13") (pintype "bidirectional"))
      (node (ref "IC2") (pin "D8") (pinfunction "DQ18_D8") (pintype "bidirectional"))
    )
    (net (code "98") (name "/RAM_D19") (class "Default")
      (node (ref "IC1") (pin "L12") (pinfunction "PH11_L12") (pintype "bidirectional"))
      (node (ref "IC2") (pin "B9") (pinfunction "DQ19_B9") (pintype "bidirectional"))
    )
    (net (code "99") (name "/RAM_D20") (class "Default")
      (node (ref "IC1") (pin "K12") (pinfunction "PH12_K12") (pintype "bidirectional"))
      (node (ref "IC2") (pin "C8") (pinfunction "DQ20_C8") (pintype "bidirectional"))
    )
    (net (code "100") (name "/RAM_D21") (class "Default")
      (node (ref "IC1") (pin "E12") (pinfunction "PH13_E12") (pintype "bidirectional"))
      (node (ref "IC2") (pin "A9") (pinfunction "DQ21_A9") (pintype "bidirectional"))
    )
    (net (code "101") (name "/RAM_D22") (class "Default")
      (node (ref "IC1") (pin "E13") (pinfunction "PH14_E13") (pintype "bidirectional"))
      (node (ref "IC2") (pin "C7") (pinfunction "DQ22_C7") (pintype "bidirectional"))
    )
    (net (code "102") (name "/RAM_D23") (class "Default")
      (node (ref "IC1") (pin "D13") (pinfunction "PH15_D13") (pintype "bidirectional"))
      (node (ref "IC2") (pin "A8") (pinfunction "DQ23_A8") (pintype "bidirectional"))
    )
    (net (code "103") (name "/RAM_D24") (class "Default")
      (node (ref "IC1") (pin "E14") (pinfunction "PI0_E14") (pintype "bidirectional"))
      (node (ref "IC2") (pin "A2") (pinfunction "DQ24_A2") (pintype "bidirectional"))
    )
    (net (code "104") (name "/RAM_D25") (class "Default")
      (node (ref "IC1") (pin "D14") (pinfunction "PI1_D14") (pintype "bidirectional"))
      (node (ref "IC2") (pin "C3") (pinfunction "DQ25_C3") (pintype "bidirectional"))
    )
    (net (code "105") (name "/RAM_D26") (class "Default")
      (node (ref "IC1") (pin "C14") (pinfunction "PI2_C14") (pintype "bidirectional"))
      (node (ref "IC2") (pin "A1") (pinfunction "DQ26_A1") (pintype "bidirectional"))
    )
    (net (code "106") (name "/RAM_D27") (class "Default")
      (node (ref "IC1") (pin "C13") (pinfunction "PI3_C13") (pintype "bidirectional"))
      (node (ref "IC2") (pin "C2") (pinfunction "DQ27_C2") (pintype "bidirectional"))
    )
    (net (code "107") (name "/RAM_D28") (class "Default")
      (node (ref "IC1") (pin "C3") (pinfunction "PI6_C3") (pintype "bidirectional"))
      (node (ref "IC2") (pin "B1") (pinfunction "DQ28_B1") (pintype "bidirectional"))
    )
    (net (code "108") (name "/RAM_D29") (class "Default")
      (node (ref "IC1") (pin "C2") (pinfunction "PI7_C2") (pintype "bidirectional"))
      (node (ref "IC2") (pin "D2") (pinfunction "DQ29_D2") (pintype "bidirectional"))
    )
    (net (code "109") (name "/RAM_D30") (class "Default")
      (node (ref "IC1") (pin "D3") (pinfunction "PI9_D3") (pintype "bidirectional"))
      (node (ref "IC2") (pin "D3") (pinfunction "DQ30_D3") (pintype "bidirectional"))
    )
    (net (code "110") (name "/RAM_D31") (class "Default")
      (node (ref "IC1") (pin "E3") (pinfunction "PI10_E3") (pintype "bidirectional"))
      (node (ref "IC2") (pin "E2") (pinfunction "DQ31_E2") (pintype "bidirectional"))
    )
    (net (code "111") (name "/RAM_M0") (class "Default")
      (node (ref "IC1") (pin "A4") (pinfunction "PE0_A4") (pintype "bidirectional"))
      (node (ref "IC2") (pin "K9") (pinfunction "DQM0_K9") (pintype "bidirectional"))
    )
    (net (code "112") (name "/RAM_M1") (class "Default")
      (node (ref "IC1") (pin "A3") (pinfunction "PE1_A3") (pintype "bidirectional"))
      (node (ref "IC2") (pin "K1") (pinfunction "DQM1_K1") (pintype "bidirectional"))
    )
    (net (code "113") (name "/RAM_M2") (class "Default")
      (node (ref "IC1") (pin "D4") (pinfunction "PI4_D4") (pintype "bidirectional"))
      (node (ref "IC2") (pin "F8") (pinfunction "DQM2_F8") (pintype "bidirectional"))
    )
    (net (code "114") (name "/RAM_M3") (class "Default")
      (node (ref "IC1") (pin "C4") (pinfunction "PI5_C4") (pintype "bidirectional"))
      (node (ref "IC2") (pin "F2") (pinfunction "DQM3_F2") (pintype "bidirectional"))
    )
    (net (code "115") (name "/RAM_~{CAS}") (class "Default")
      (node (ref "IC1") (pin "B7") (pinfunction "PG15_B7") (pintype "bidirectional"))
      (node (ref "IC2") (pin "K7") (pinfunction "~{CAS}_K7") (pintype "bidirectional"))
    )
    (net (code "116") (name "/RAM_~{CS}") (class "Default")
      (node (ref "IC1") (pin "G4") (pinfunction "PH3_G4") (pintype "bidirectional"))
      (node (ref "IC2") (pin "J8") (pinfunction "~{CS}_J8") (pintype "bidirectional"))
    )
    (net (code "117") (name "/RAM_~{RAS}") (class "Default")
      (node (ref "IC1") (pin "R6") (pinfunction "PF11_R6") (pintype "bidirectional"))
      (node (ref "IC2") (pin "J9") (pinfunction "~{RAS}_J9") (pintype "bidirectional"))
    )
    (net (code "118") (name "/RAM_~{WE}") (class "Default")
      (node (ref "IC1") (pin "J4") (pinfunction "PH5_J4") (pintype "bidirectional"))
      (node (ref "IC2") (pin "K8") (pinfunction "~{WE}_K8") (pintype "bidirectional"))
    )
    (net (code "119") (name "/SAI_BCK") (class "Default")
      (node (ref "IC1") (pin "B2") (pinfunction "PE5_B2") (pintype "bidirectional"))
      (node (ref "IC3") (pin "6") (pinfunction "SCLK_6") (pintype "bidirectional"))
    )
    (net (code "120") (name "/SAI_LRCK") (class "Default")
      (node (ref "IC1") (pin "B1") (pinfunction "PE4_B1") (pintype "bidirectional"))
      (node (ref "IC3") (pin "4") (pinfunction "LRCK_4") (pintype "bidirectional"))
    )
    (net (code "121") (name "/SAI_MCLK") (class "Default")
      (node (ref "IC1") (pin "J14") (pinfunction "PG7_J14") (pintype "bidirectional"))
      (node (ref "IC3") (pin "5") (pinfunction "MCLK_5") (pintype "bidirectional"))
    )
    (net (code "122") (name "/SAI_SDI") (class "Default")
      (node (ref "IC1") (pin "B3") (pinfunction "PE6_B3") (pintype "bidirectional"))
      (node (ref "IC3") (pin "7") (pinfunction "SDOUT1_7") (pintype "bidirectional"))
    )
    (net (code "123") (name "/SAI_SDO") (class "Default")
      (node (ref "IC1") (pin "A1") (pinfunction "PE3_A1") (pintype "bidirectional"))
      (node (ref "IC3") (pin "2") (pinfunction "SDIN1_2") (pintype "bidirectional"))
    )
    (net (code "124") (name "/SPI3_MISO") (class "Default")
      (node (ref "IC1") (pin "B13") (pinfunction "PC11_B13") (pintype "bidirectional"))
      (node (ref "JP2") (pin "20") (pinfunction "20_20") (pintype "passive"))
    )
    (net (code "125") (name "/SPI3_MOSI") (class "Default")
      (node (ref "IC1") (pin "A12") (pinfunction "PC12_A12") (pintype "bidirectional"))
      (node (ref "JP2") (pin "22") (pinfunction "22_22") (pintype "passive"))
    )
    (net (code "126") (name "/SPI3_SCK") (class "Default")
      (node (ref "IC1") (pin "B14") (pinfunction "PC10_B14") (pintype "bidirectional"))
      (node (ref "JP2") (pin "18") (pinfunction "18_18") (pintype "passive"))
    )
    (net (code "127") (name "/SPI6_MISO") (class "Default")
      (node (ref "IC1") (pin "A9") (pinfunction "PB4_A9") (pintype "bidirectional"))
      (node (ref "JP2") (pin "19") (pinfunction "19_19") (pintype "passive"))
    )
    (net (code "128") (name "/SPI6_MOSI") (class "Default")
      (node (ref "IC1") (pin "A7") (pinfunction "PG14_A7") (pintype "bidirectional"))
      (node (ref "JP2") (pin "21") (pinfunction "21_21") (pintype "passive"))
    )
    (net (code "129") (name "/SPI6_SCK") (class "Default")
      (node (ref "IC1") (pin "A8") (pinfunction "PG13_A8") (pintype "bidirectional"))
      (node (ref "JP2") (pin "17") (pinfunction "17_17") (pintype "passive"))
    )
    (net (code "130") (name "/SWDCLK") (class "Default")
      (node (ref "IC1") (pin "A14") (pinfunction "PA14_A14") (pintype "bidirectional"))
      (node (ref "J1") (pin "4") (pinfunction "SWDCLK/TCK_4") (pintype "bidirectional"))
    )
    (net (code "131") (name "/SWDIO") (class "Default")
      (node (ref "IC1") (pin "A15") (pinfunction "PA13_A15") (pintype "bidirectional"))
      (node (ref "J1") (pin "2") (pinfunction "SWDIO/TMS_2") (pintype "bidirectional"))
    )
    (net (code "132") (name "/SWO") (class "Default")
      (node (ref "IC1") (pin "A10") (pinfunction "PB3_A10") (pintype "bidirectional"))
      (node (ref "J1") (pin "6") (pinfunction "SWO/TDO_6") (pintype "bidirectional"))
    )
    (net (code "133") (name "/TIM2_CH1") (class "Default")
      (node (ref "IC1") (pin "A13") (pinfunction "PA15_A13") (pintype "bidirectional"))
      (node (ref "JP1") (pin "19") (pinfunction "19_19") (pintype "passive"))
    )
    (net (code "134") (name "/TIM2_CH2") (class "Default")
      (node (ref "IC1") (pin "N2") (pinfunction "PA1_N2") (pintype "bidirectional"))
      (node (ref "JP1") (pin "20") (pinfunction "20_20") (pintype "passive"))
    )
    (net (code "135") (name "/TIM3_CH1") (class "Default")
      (node (ref "IC1") (pin "H15") (pinfunction "PC6_H15") (pintype "bidirectional"))
      (node (ref "JP1") (pin "21") (pinfunction "21_21") (pintype "passive"))
    )
    (net (code "136") (name "/TIM3_CH2") (class "Default")
      (node (ref "IC1") (pin "G15") (pinfunction "PC7_G15") (pintype "bidirectional"))
      (node (ref "JP1") (pin "22") (pinfunction "22_22") (pintype "passive"))
    )
    (net (code "137") (name "/TIM4_CH1") (class "Default")
      (node (ref "IC1") (pin "N13") (pinfunction "PD12_N13") (pintype "bidirectional"))
      (node (ref "JP1") (pin "23") (pinfunction "23_23") (pintype "passive"))
    )
    (net (code "138") (name "/TIM4_CH2") (class "Default")
      (node (ref "IC1") (pin "M15") (pinfunction "PD13_M15") (pintype "bidirectional"))
      (node (ref "JP1") (pin "24") (pinfunction "24_24") (pintype "passive"))
    )
    (net (code "139") (name "/UART5_RX") (class "Default")
      (node (ref "IC1") (pin "A6") (pinfunction "PB5_A6") (pintype "bidirectional"))
      (node (ref "JP2") (pin "15") (pinfunction "15_15") (pintype "passive"))
    )
    (net (code "140") (name "/UART5_TX") (class "Default")
      (node (ref "IC1") (pin "B6") (pinfunction "PB6_B6") (pintype "bidirectional"))
      (node (ref "JP2") (pin "13") (pinfunction "13_13") (pintype "passive"))
    )
    (net (code "141") (name "/UART7_RX") (class "Default")
      (node (ref "IC1") (pin "F15") (pinfunction "PA8_F15") (pintype "bidirectional"))
      (node (ref "JP2") (pin "16") (pinfunction "16_16") (pintype "passive"))
    )
    (net (code "142") (name "/UART7_TX") (class "Default")
      (node (ref "IC1") (pin "K1") (pinfunction "PF7_K1") (pintype "bidirectional"))
      (node (ref "JP2") (pin "14") (pinfunction "14_14") (pintype "passive"))
    )
    (net (code "143") (name "/USBD_D+") (class "Default")
      (node (ref "CN1") (pin "3") (pinfunction "D+_3") (pintype "bidirectional"))
      (node (ref "IC1") (pin "B15") (pinfunction "PA12_B15") (pintype "bidirectional"))
      (node (ref "JP2") (pin "7") (pinfunction "7_7") (pintype "passive"))
    )
    (net (code "144") (name "/USBD_D-") (class "Default")
      (node (ref "CN1") (pin "2") (pinfunction "D-_2") (pintype "bidirectional"))
      (node (ref "IC1") (pin "C15") (pinfunction "PA11_C15") (pintype "bidirectional"))
      (node (ref "JP2") (pin "5") (pinfunction "5_5") (pintype "passive"))
    )
    (net (code "145") (name "/USBD_ID") (class "Default")
      (node (ref "CN1") (pin "4") (pinfunction "ID_4") (pintype "bidirectional"))
      (node (ref "IC1") (pin "D15") (pinfunction "PA10_D15") (pintype "bidirectional"))
      (node (ref "JP2") (pin "9") (pinfunction "9_9") (pintype "passive"))
    )
    (net (code "146") (name "/USBD_VBUS") (class "Default")
      (node (ref "CN1") (pin "1") (pinfunction "VCC_1") (pintype "bidirectional"))
      (node (ref "IC1") (pin "E15") (pinfunction "PA9_E15") (pintype "bidirectional"))
      (node (ref "JP2") (pin "3") (pinfunction "3_3") (pintype "passive"))
    )
    (net (code "147") (name "/USBH_D+") (class "Default")
      (node (ref "IC1") (pin "R15") (pinfunction "PB15_R15") (pintype "bidirectional"))
      (node (ref "JP2") (pin "8") (pinfunction "8_8") (pintype "passive"))
    )
    (net (code "148") (name "/USBH_D-") (class "Default")
      (node (ref "IC1") (pin "R14") (pinfunction "PB14_R14") (pintype "bidirectional"))
      (node (ref "JP2") (pin "6") (pinfunction "6_6") (pintype "passive"))
    )
    (net (code "149") (name "/USBH_ID") (class "Default")
      (node (ref "IC1") (pin "P12") (pinfunction "PB12_P12") (pintype "bidirectional"))
      (node (ref "JP2") (pin "10") (pinfunction "10_10") (pintype "passive"))
    )
    (net (code "150") (name "/USBH_VBUS") (class "Default")
      (node (ref "IC1") (pin "P13") (pinfunction "PB13_P13") (pintype "bidirectional"))
      (node (ref "JP2") (pin "4") (pinfunction "4_4") (pintype "passive"))
    )
    (net (code "151") (name "AGND") (class "Default")
      (node (ref "C11") (pin "2") (pinfunction "2_2") (pintype "passive"))
      (node (ref "C12") (pin "2") (pinfunction "2_2") (pintype "passive"))
      (node (ref "C15") (pin "2") (pinfunction "2_2") (pintype "passive"))
      (node (ref "C18") (pin "2") (pinfunction "2_2") (pintype "passive"))
      (node (ref "C21") (pin "2") (pinfunction "2_2") (pintype "passive"))
      (node (ref "C24") (pin "2") (pinfunction "2_2") (pintype "passive"))
      (node (ref "C25") (pin "2") (pinfunction "2_2") (pintype "passive"))
      (node (ref "C27") (pin "2") (pinfunction "2_2") (pintype "passive"))
      (node (ref "C29") (pin "2") (pinfunction "2_2") (pintype "passive"))
      (node (ref "C31") (pin "-") (pinfunction "-_-") (pintype "passive"))
      (node (ref "C32") (pin "2") (pinfunction "2_2") (pintype "passive"))
      (node (ref "C35") (pin "2") (pinfunction "2_2") (pintype "passive"))
      (node (ref "IC1") (pin "M1") (pinfunction "VSSA_M1") (pintype "bidirectional"))
      (node (ref "IC1") (pin "N1") (pinfunction "VREF-_N1") (pintype "bidirectional"))
      (node (ref "IC3") (pin "21") (pinfunction "GND_21") (pintype "bidirectional"))
      (node (ref "IC3") (pin "41") (pinfunction "GND_41") (pintype "bidirectional"))
      (node (ref "IC3") (pin "9") (pinfunction "GND_9") (pintype "bidirectional"))
      (node (ref "JP1") (pin "33") (pinfunction "33_33") (pintype "passive"))
      (node (ref "JP1") (pin "43") (pinfunction "43_43") (pintype "passive"))
      (node (ref "JP1") (pin "44") (pinfunction "44_44") (pintype "passive"))
      (node (ref "JP1") (pin "45") (pinfunction "45_45") (pintype "passive"))
      (node (ref "JP1") (pin "46") (pinfunction "46_46") (pintype "passive"))
      (node (ref "JP1") (pin "47") (pinfunction "47_47") (pintype "passive"))
      (node (ref "JP1") (pin "48") (pinfunction "48_48") (pintype "passive"))
      (node (ref "JP2") (pin "25") (pinfunction "25_25") (pintype "passive"))
      (node (ref "JP2") (pin "26") (pinfunction "26_26") (pintype "passive"))
      (node (ref "JP2") (pin "29") (pinfunction "29_29") (pintype "passive"))
      (node (ref "JP2") (pin "39") (pinfunction "39_39") (pintype "passive"))
      (node (ref "JP2") (pin "40") (pinfunction "40_40") (pintype "passive"))
      (node (ref "JP2") (pin "41") (pinfunction "41_41") (pintype "passive"))
      (node (ref "JP2") (pin "42") (pinfunction "42_42") (pintype "passive"))
      (node (ref "JP2") (pin "43") (pinfunction "43_43") (pintype "passive"))
      (node (ref "JP2") (pin "44") (pinfunction "44_44") (pintype "passive"))
      (node (ref "JP2") (pin "45") (pinfunction "45_45") (pintype "passive"))
      (node (ref "JP2") (pin "46") (pinfunction "46_46") (pintype "passive"))
      (node (ref "JP2") (pin "47") (pinfunction "47_47") (pintype "passive"))
      (node (ref "JP2") (pin "48") (pinfunction "48_48") (pintype "passive"))
      (node (ref "L1") (pin "1") (pinfunction "1_1") (pintype "passive"))
      (node (ref "R5") (pin "1") (pinfunction "1_1") (pintype "passive"))
      (node (ref "R6") (pin "1") (pinfunction "1_1") (pintype "passive"))
    )
    (net (code "152") (name "GND") (class "Default")
      (node (ref "C1") (pin "2") (pinfunction "2_2") (pintype "passive"))
      (node (ref "C10") (pin "2") (pinfunction "2_2") (pintype "passive"))
      (node (ref "C13") (pin "2") (pinfunction "2_2") (pintype "passive"))
      (node (ref "C14") (pin "2") (pinfunction "2_2") (pintype "passive"))
      (node (ref "C16") (pin "-") (pinfunction "-_-") (pintype "passive"))
      (node (ref "C17") (pin "2") (pinfunction "2_2") (pintype "passive"))
      (node (ref "C19") (pin "-") (pinfunction "-_-") (pintype "passive"))
      (node (ref "C2") (pin "2") (pinfunction "2_2") (pintype "passive"))
      (node (ref "C20") (pin "2") (pinfunction "2_2") (pintype "passive"))
      (node (ref "C22") (pin "2") (pinfunction "2_2") (pintype "passive"))
      (node (ref "C23") (pin "2") (pinfunction "2_2") (pintype "passive"))
      (node (ref "C26") (pin "2") (pinfunction "2_2") (pintype "passive"))
      (node (ref "C3") (pin "2") (pinfunction "2_2") (pintype "passive"))
      (node (ref "C38") (pin "1") (pinfunction "1_1") (pintype "passive"))
      (node (ref "C39") (pin "2") (pinfunction "2_2") (pintype "passive"))
      (node (ref "C4") (pin "2") (pinfunction "2_2") (pintype "passive"))
      (node (ref "C40") (pin "2") (pinfunction "2_2") (pintype "passive"))
      (node (ref "C5") (pin "2") (pinfunction "2_2") (pintype "passive"))
      (node (ref "C6") (pin "2") (pinfunction "2_2") (pintype "passive"))
      (node (ref "C7") (pin "2") (pinfunction "2_2") (pintype "passive"))
      (node (ref "C8") (pin "2") (pinfunction "2_2") (pintype "passive"))
      (node (ref "C9") (pin "2") (pinfunction "2_2") (pintype "passive"))
      (node (ref "C90") (pin "2") (pinfunction "2_2") (pintype "passive"))
      (node (ref "CN1") (pin "5") (pinfunction "GND_5") (pintype "bidirectional"))
      (node (ref "CN1") (pin "G") (pinfunction "SHIELD_G") (pintype "bidirectional"))
      (node (ref "CN1") (pin "G2") (pinfunction "SHIELD_G2") (pintype "bidirectional"))
      (node (ref "CN1") (pin "G3") (pinfunction "SHIELD_G3") (pintype "bidirectional"))
      (node (ref "CN1") (pin "G4") (pinfunction "SHIELD_G4") (pintype "bidirectional"))
      (node (ref "IC1") (pin "D5") (pinfunction "VSS_1_D5") (pintype "bidirectional"))
      (node (ref "IC1") (pin "D7") (pinfunction "VSS_2_D7") (pintype "bidirectional"))
      (node (ref "IC1") (pin "D8") (pinfunction "VSS_3_D8") (pintype "bidirectional"))
      (node (ref "IC1") (pin "D9") (pinfunction "VSS_4_D9") (pintype "bidirectional"))
      (node (ref "IC1") (pin "F10") (pinfunction "VSS_10_F10") (pintype "bidirectional"))
      (node (ref "IC1") (pin "F12") (pinfunction "VSS_11_F12") (pintype "bidirectional"))
      (node (ref "IC1") (pin "F2") (pinfunction "VSS_5_F2") (pintype "bidirectional"))
      (node (ref "IC1") (pin "F6") (pinfunction "VSS_6_F6") (pintype "bidirectional"))
      (node (ref "IC1") (pin "F7") (pinfunction "VSS_7_F7") (pintype "bidirectional"))
      (node (ref "IC1") (pin "F8") (pinfunction "VSS_8_F8") (pintype "bidirectional"))
      (node (ref "IC1") (pin "F9") (pinfunction "VSS_9_F9") (pintype "bidirectional"))
      (node (ref "IC1") (pin "G10") (pinfunction "VSS_17_G10") (pintype "bidirectional"))
      (node (ref "IC1") (pin "G12") (pinfunction "VSS_18_G12") (pintype "bidirectional"))
      (node (ref "IC1") (pin "G2") (pinfunction "VSS_12_G2") (pintype "bidirectional"))
      (node (ref "IC1") (pin "G6") (pinfunction "VSS_13_G6") (pintype "bidirectional"))
      (node (ref "IC1") (pin "G7") (pinfunction "VSS_14_G7") (pintype "bidirectional"))
      (node (ref "IC1") (pin "G8") (pinfunction "VSS_15_G8") (pintype "bidirectional"))
      (node (ref "IC1") (pin "G9") (pinfunction "VSS_16_G9") (pintype "bidirectional"))
      (node (ref "IC1") (pin "H10") (pinfunction "VSS_23_H10") (pintype "bidirectional"))
      (node (ref "IC1") (pin "H12") (pinfunction "VSS_24_H12") (pintype "bidirectional"))
      (node (ref "IC1") (pin "H6") (pinfunction "VSS_19_H6") (pintype "bidirectional"))
      (node (ref "IC1") (pin "H7") (pinfunction "VSS_20_H7") (pintype "bidirectional"))
      (node (ref "IC1") (pin "H8") (pinfunction "VSS_21_H8") (pintype "bidirectional"))
      (node (ref "IC1") (pin "H9") (pinfunction "VSS_22_H9") (pintype "bidirectional"))
      (node (ref "IC1") (pin "J10") (pinfunction "VSS_29_J10") (pintype "bidirectional"))
      (node (ref "IC1") (pin "J6") (pinfunction "VSS_25_J6") (pintype "bidirectional"))
      (node (ref "IC1") (pin "J7") (pinfunction "VSS_26_J7") (pintype "bidirectional"))
      (node (ref "IC1") (pin "J8") (pinfunction "VSS_27_J8") (pintype "bidirectional"))
      (node (ref "IC1") (pin "J9") (pinfunction "VSS_28_J9") (pintype "bidirectional"))
      (node (ref "IC1") (pin "K10") (pinfunction "VSS_34_K10") (pintype "bidirectional"))
      (node (ref "IC1") (pin "K6") (pinfunction "VSS_30_K6") (pintype "bidirectional"))
      (node (ref "IC1") (pin "K7") (pinfunction "VSS_31_K7") (pintype "bidirectional"))
      (node (ref "IC1") (pin "K8") (pinfunction "VSS_32_K8") (pintype "bidirectional"))
      (node (ref "IC1") (pin "K9") (pinfunction "VSS_33_K9") (pintype "bidirectional"))
      (node (ref "IC1") (pin "L4") (pinfunction "VSS_35_L4") (pintype "bidirectional"))
      (node (ref "IC1") (pin "M8") (pinfunction "VSS_36_M8") (pintype "bidirectional"))
      (node (ref "IC1") (pin "M9") (pinfunction "VSS_37_M9") (pintype "bidirectional"))
      (node (ref "IC2") (pin "A3") (pinfunction "VSS_1_A3") (pintype "bidirectional"))
      (node (ref "IC2") (pin "B3") (pinfunction "VSSQ_1_B3") (pintype "bidirectional"))
      (node (ref "IC2") (pin "B8") (pinfunction "VSSQ_2_B8") (pintype "bidirectional"))
      (node (ref "IC2") (pin "C1") (pinfunction "VSSQ_3_C1") (pintype "bidirectional"))
      (node (ref "IC2") (pin "D1") (pinfunction "VSSQ_4_D1") (pintype "bidirectional"))
      (node (ref "IC2") (pin "E9") (pinfunction "VSSQ_5_E9") (pintype "bidirectional"))
      (node (ref "IC2") (pin "F1") (pinfunction "VSS_2_F1") (pintype "bidirectional"))
      (node (ref "IC2") (pin "L3") (pinfunction "VSS_3_L3") (pintype "bidirectional"))
      (node (ref "IC2") (pin "L9") (pinfunction "VSSQ_6_L9") (pintype "bidirectional"))
      (node (ref "IC2") (pin "M1") (pinfunction "VSSQ_7_M1") (pintype "bidirectional"))
      (node (ref "IC2") (pin "N1") (pinfunction "VSSQ_8_N1") (pintype "bidirectional"))
      (node (ref "IC2") (pin "P3") (pinfunction "VSSQ_9_P3") (pintype "bidirectional"))
      (node (ref "IC2") (pin "P8") (pinfunction "VSSQ_10_P8") (pintype "bidirectional"))
      (node (ref "IC2") (pin "R3") (pinfunction "VSS_4_R3") (pintype "bidirectional"))
      (node (ref "IC9") (pin "4") (pinfunction "VSS_4") (pintype "bidirectional"))
      (node (ref "J1") (pin "3") (pinfunction "GND_3") (pintype "bidirectional"))
      (node (ref "J1") (pin "5") (pinfunction "GND_5") (pintype "bidirectional"))
      (node (ref "J1") (pin "7") (pinfunction "GND_7") (pintype "bidirectional"))
      (node (ref "J1") (pin "9") (pinfunction "GND_9") (pintype "bidirectional"))
      (node (ref "JP1") (pin "15") (pinfunction "15_15") (pintype "passive"))
      (node (ref "JP1") (pin "16") (pinfunction "16_16") (pintype "passive"))
      (node (ref "JP2") (pin "11") (pinfunction "11_11") (pintype "passive"))
      (node (ref "JP2") (pin "12") (pinfunction "12_12") (pintype "passive"))
      (node (ref "L1") (pin "2") (pinfunction "2_2") (pintype "passive"))
      (node (ref "R1") (pin "1") (pinfunction "1_1") (pintype "passive"))
      (node (ref "U3") (pin "1") (pinfunction "ADJ_1") (pintype "input"))
    )
    (net (code "153") (name "Net-(IC1-PH0-_OSC_IN)") (class "Default")
      (node (ref "C22") (pin "1") (pinfunction "1_1") (pintype "passive"))
      (node (ref "IC1") (pin "G1") (pinfunction "PH0-_OSC_IN_G1") (pintype "bidirectional"))
      (node (ref "Y1") (pin "2") (pinfunction "2_2") (pintype "passive"))
    )
    (net (code "154") (name "Net-(IC1-PH1-_OSC___OUT)") (class "Default")
      (node (ref "C23") (pin "1") (pinfunction "1_1") (pintype "passive"))
      (node (ref "IC1") (pin "H1") (pinfunction "PH1-_OSC___OUT_H1") (pintype "bidirectional"))
      (node (ref "Y1") (pin "1") (pinfunction "1_1") (pintype "passive"))
    )
    (net (code "155") (name "Net-(IC1-VCAP_1)") (class "Default")
      (node (ref "C13") (pin "1") (pinfunction "1_1") (pintype "passive"))
      (node (ref "IC1") (pin "F13") (pinfunction "VCAP_1_F13") (pintype "bidirectional"))
    )
    (net (code "156") (name "Net-(IC1-VCAP_2)") (class "Default")
      (node (ref "C14") (pin "1") (pinfunction "1_1") (pintype "passive"))
      (node (ref "IC1") (pin "M10") (pinfunction "VCAP_2_M10") (pintype "bidirectional"))
    )
    (net (code "157") (name "Net-(IC3-AD0)") (class "Default")
      (node (ref "IC3") (pin "37") (pinfunction "SDOUT2/AD2_37") (pintype "bidirectional"))
      (node (ref "IC3") (pin "38") (pinfunction "AD1_38") (pintype "bidirectional"))
      (node (ref "IC3") (pin "39") (pinfunction "AD0_39") (pintype "bidirectional"))
      (node (ref "R6") (pin "2") (pinfunction "2_2") (pintype "passive"))
    )
    (net (code "158") (name "Net-(IC3-FILT+)") (class "Default")
      (node (ref "C35") (pin "1") (pinfunction "1_1") (pintype "passive"))
      (node (ref "IC3") (pin "19") (pinfunction "FILT+_19") (pintype "bidirectional"))
    )
    (net (code "159") (name "Net-(IC3-VBIAS)") (class "Default")
      (node (ref "C28") (pin "-") (pinfunction "-_-") (pintype "passive"))
      (node (ref "IC3") (pin "24") (pinfunction "VBIAS_24") (pintype "bidirectional"))
    )
    (net (code "160") (name "Net-(IC3-VDREG)") (class "Default")
      (node (ref "C18") (pin "1") (pinfunction "1_1") (pintype "passive"))
      (node (ref "C31") (pin "+") (pinfunction "+_+") (pintype "passive"))
      (node (ref "IC3") (pin "10") (pinfunction "VDREG_10") (pintype "bidirectional"))
    )
    (net (code "161") (name "Net-(IC3-VQ)") (class "Default")
      (node (ref "C32") (pin "1") (pinfunction "1_1") (pintype "passive"))
      (node (ref "IC3") (pin "22") (pinfunction "VQ_22") (pintype "bidirectional"))
    )
    (net (code "162") (name "unconnected-(IC1-PB2-PadM6)") (class "Default")
      (node (ref "IC1") (pin "M6") (pinfunction "PB2_M6") (pintype "bidirectional"))
    )
    (net (code "163") (name "unconnected-(IC1-PB9-PadB4)") (class "Default")
      (node (ref "IC1") (pin "B4") (pinfunction "PB9_B4") (pintype "bidirectional"))
    )
    (net (code "164") (name "unconnected-(IC1-PD3-PadD11)") (class "Default")
      (node (ref "IC1") (pin "D11") (pinfunction "PD3_D11") (pintype "bidirectional"))
    )
    (net (code "165") (name "unconnected-(IC1-PD4-PadD10)") (class "Default")
      (node (ref "IC1") (pin "D10") (pinfunction "PD4_D10") (pintype "bidirectional"))
    )
    (net (code "166") (name "unconnected-(IC1-PD5-PadC11)") (class "Default")
      (node (ref "IC1") (pin "C11") (pinfunction "PD5_C11") (pintype "bidirectional"))
    )
    (net (code "167") (name "unconnected-(IC1-PD6-PadB11)") (class "Default")
      (node (ref "IC1") (pin "B11") (pinfunction "PD6_B11") (pintype "bidirectional"))
    )
    (net (code "168") (name "unconnected-(IC1-PD7-PadA11)") (class "Default")
      (node (ref "IC1") (pin "A11") (pinfunction "PD7_A11") (pintype "bidirectional"))
    )
    (net (code "169") (name "unconnected-(IC1-PD11-PadN14)") (class "Default")
      (node (ref "IC1") (pin "N14") (pinfunction "PD11_N14") (pintype "bidirectional"))
    )
    (net (code "170") (name "unconnected-(IC1-PG9-PadC10)") (class "Default")
      (node (ref "IC1") (pin "C10") (pinfunction "PG9_C10") (pintype "bidirectional"))
    )
    (net (code "171") (name "unconnected-(IC1-PH6-PadM11)") (class "Default")
      (node (ref "IC1") (pin "M11") (pinfunction "PH6_M11") (pintype "bidirectional"))
    )
    (net (code "172") (name "unconnected-(IC1-PH7-PadN12)") (class "Default")
      (node (ref "IC1") (pin "N12") (pinfunction "PH7_N12") (pintype "bidirectional"))
    )
    (net (code "173") (name "unconnected-(IC1-PI8-PadD2)") (class "Default")
      (node (ref "IC1") (pin "D2") (pinfunction "PI8_D2") (pintype "bidirectional"))
    )
    (net (code "174") (name "unconnected-(IC1-VBAT-PadC1)") (class "Default")
      (node (ref "IC1") (pin "C1") (pinfunction "VBAT_C1") (pintype "bidirectional"))
    )
    (net (code "175") (name "unconnected-(IC2-NC_1-PadE3)") (class "Default")
      (node (ref "IC2") (pin "E3") (pinfunction "NC_1_E3") (pintype "bidirectional"))
    )
    (net (code "176") (name "unconnected-(IC2-NC_2-PadE7)") (class "Default")
      (node (ref "IC2") (pin "E7") (pinfunction "NC_2_E7") (pintype "bidirectional"))
    )
    (net (code "177") (name "unconnected-(IC2-NC_3-PadH7)") (class "Default")
      (node (ref "IC2") (pin "H7") (pinfunction "NC_3_H7") (pintype "bidirectional"))
    )
    (net (code "178") (name "unconnected-(IC2-NC_4-PadK2)") (class "Default")
      (node (ref "IC2") (pin "K2") (pinfunction "NC_4_K2") (pintype "bidirectional"))
    )
    (net (code "179") (name "unconnected-(IC2-NC_5-PadK3)") (class "Default")
      (node (ref "IC2") (pin "K3") (pinfunction "NC_5_K3") (pintype "bidirectional"))
    )
    (net (code "180") (name "unconnected-(IC3-SDIN2-Pad3)") (class "Default")
      (node (ref "IC3") (pin "3") (pinfunction "SDIN2_3") (pintype "bidirectional"))
    )
    (net (code "181") (name "unconnected-(IC3-~{INT}-Pad36)") (class "Default")
      (node (ref "IC3") (pin "36") (pinfunction "~{INT}_36") (pintype "bidirectional"))
    )
    (net (code "182") (name "unconnected-(J1-NC{slash}TDI-Pad8)") (class "Default")
      (node (ref "J1") (pin "8") (pinfunction "NC/TDI_8") (pintype "bidirectional"))
    )
  )
)
